# spotlight.net
KiCad netlist of a schematic drawn in EAGLE
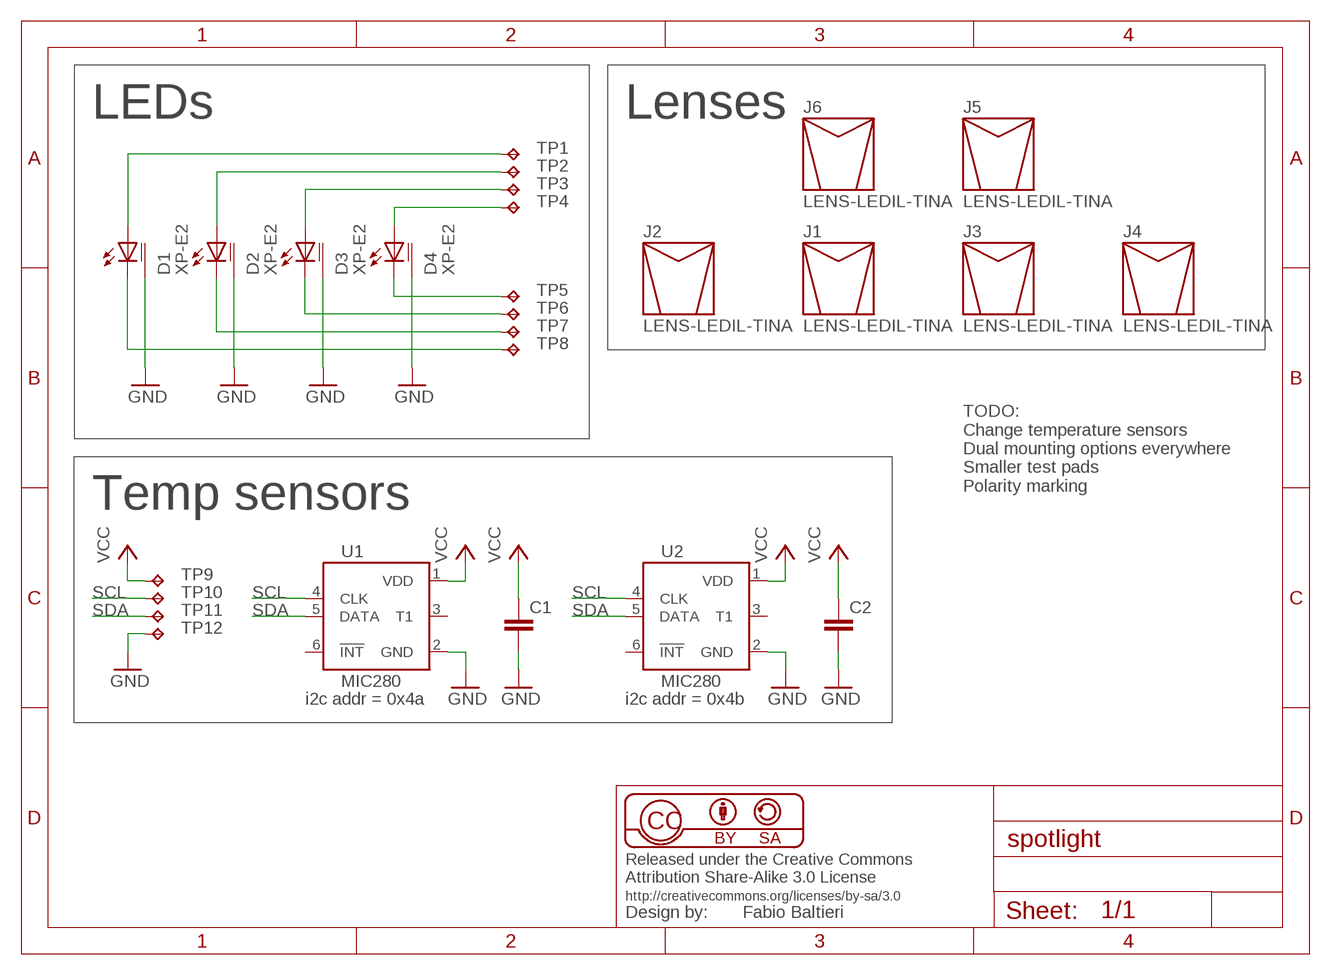
[diagram p0: schematic, sheet 1]

(export (version "E")
  (design (tool "Eeschema 10.0.6"))
  (components
    (comp (ref "C1")
      (value "C0603")
      (footprint "eagle-import:0603")
      (libsource (lib "eagle-import") (part "C0603"))
    )
    (comp (ref "C2")
      (value "C0603")
      (footprint "eagle-import:0603")
      (libsource (lib "eagle-import") (part "C0603"))
    )
    (comp (ref "D1")
      (value "XP-E2")
      (footprint "eagle-import:CREE_XPE")
      (libsource (lib "eagle-import") (part "LED_CREE-XP-E"))
    )
    (comp (ref "D2")
      (value "XP-E2")
      (footprint "eagle-import:CREE_XPE")
      (libsource (lib "eagle-import") (part "LED_CREE-XP-E"))
    )
    (comp (ref "D3")
      (value "XP-E2")
      (footprint "eagle-import:CREE_XPE")
      (libsource (lib "eagle-import") (part "LED_CREE-XP-E"))
    )
    (comp (ref "D4")
      (value "XP-E2")
      (footprint "eagle-import:CREE_XPE")
      (libsource (lib "eagle-import") (part "LED_CREE-XP-E"))
    )
    (comp (ref "J1")
      (value "LENS-LEDIL-TINA")
      (footprint "eagle-import:LEDIL-TINA")
      (libsource (lib "eagle-import") (part "LENS-LEDIL-TINA"))
    )
    (comp (ref "J2")
      (value "LENS-LEDIL-TINA")
      (footprint "eagle-import:LEDIL-TINA")
      (libsource (lib "eagle-import") (part "LENS-LEDIL-TINA"))
    )
    (comp (ref "J3")
      (value "LENS-LEDIL-TINA")
      (footprint "eagle-import:LEDIL-TINA")
      (libsource (lib "eagle-import") (part "LENS-LEDIL-TINA"))
    )
    (comp (ref "J4")
      (value "LENS-LEDIL-TINA")
      (footprint "eagle-import:LEDIL-TINA")
      (libsource (lib "eagle-import") (part "LENS-LEDIL-TINA"))
    )
    (comp (ref "J5")
      (value "LENS-LEDIL-TINA")
      (footprint "eagle-import:LEDIL-TINA")
      (libsource (lib "eagle-import") (part "LENS-LEDIL-TINA"))
    )
    (comp (ref "J6")
      (value "LENS-LEDIL-TINA")
      (footprint "eagle-import:LEDIL-TINA")
      (libsource (lib "eagle-import") (part "LENS-LEDIL-TINA"))
    )
    (comp (ref "TP1")
      (value "TPTP18R")
      (footprint "eagle-import:TP18R")
      (libsource (lib "eagle-import") (part "TPTP18R"))
    )
    (comp (ref "TP2")
      (value "TPTP18R")
      (footprint "eagle-import:TP18R")
      (libsource (lib "eagle-import") (part "TPTP18R"))
    )
    (comp (ref "TP3")
      (value "TPTP18R")
      (footprint "eagle-import:TP18R")
      (libsource (lib "eagle-import") (part "TPTP18R"))
    )
    (comp (ref "TP4")
      (value "TPTP18R")
      (footprint "eagle-import:TP18R")
      (libsource (lib "eagle-import") (part "TPTP18R"))
    )
    (comp (ref "TP5")
      (value "TPTP18R")
      (footprint "eagle-import:TP18R")
      (libsource (lib "eagle-import") (part "TPTP18R"))
    )
    (comp (ref "TP6")
      (value "TPTP18R")
      (footprint "eagle-import:TP18R")
      (libsource (lib "eagle-import") (part "TPTP18R"))
    )
    (comp (ref "TP7")
      (value "TPTP18R")
      (footprint "eagle-import:TP18R")
      (libsource (lib "eagle-import") (part "TPTP18R"))
    )
    (comp (ref "TP8")
      (value "TPTP18R")
      (footprint "eagle-import:TP18R")
      (libsource (lib "eagle-import") (part "TPTP18R"))
    )
    (comp (ref "TP9")
      (value "TPTP14R")
      (footprint "eagle-import:TP14R")
      (libsource (lib "eagle-import") (part "TPTP14R"))
    )
    (comp (ref "TP10")
      (value "TPTP14R")
      (footprint "eagle-import:TP14R")
      (libsource (lib "eagle-import") (part "TPTP14R"))
    )
    (comp (ref "TP11")
      (value "TPTP14R")
      (footprint "eagle-import:TP14R")
      (libsource (lib "eagle-import") (part "TPTP14R"))
    )
    (comp (ref "TP12")
      (value "TPTP14R")
      (footprint "eagle-import:TP14R")
      (libsource (lib "eagle-import") (part "TPTP14R"))
    )
    (comp (ref "U1")
      (value "MIC280")
      (footprint "eagle-import:SOT23-6L")
      (libsource (lib "eagle-import") (part "MIC280"))
    )
    (comp (ref "U2")
      (value "MIC280")
      (footprint "eagle-import:SOT23-6L")
      (libsource (lib "eagle-import") (part "MIC280"))
    )
  )
  (nets
    (net (code "1") (name "/SCL") (class "Default")
      (node (ref "TP10") (pin "TP") (pinfunction "TP_TP") (pintype "input"))
      (node (ref "U1") (pin "4") (pinfunction "CLK_4") (pintype "bidirectional"))
      (node (ref "U2") (pin "4") (pinfunction "CLK_4") (pintype "bidirectional"))
    )
    (net (code "2") (name "/SDA") (class "Default")
      (node (ref "TP11") (pin "TP") (pinfunction "TP_TP") (pintype "input"))
      (node (ref "U1") (pin "5") (pinfunction "DATA_5") (pintype "bidirectional"))
      (node (ref "U2") (pin "5") (pinfunction "DATA_5") (pintype "bidirectional"))
    )
    (net (code "3") (name "GND") (class "Default")
      (node (ref "C1") (pin "2") (pinfunction "2_2") (pintype "passive"))
      (node (ref "C2") (pin "2") (pinfunction "2_2") (pintype "passive"))
      (node (ref "D1") (pin "TH") (pinfunction "TH_TH") (pintype "passive"))
      (node (ref "D2") (pin "TH") (pinfunction "TH_TH") (pintype "passive"))
      (node (ref "D3") (pin "TH") (pinfunction "TH_TH") (pintype "passive"))
      (node (ref "D4") (pin "TH") (pinfunction "TH_TH") (pintype "passive"))
      (node (ref "TP12") (pin "TP") (pinfunction "TP_TP") (pintype "input"))
      (node (ref "U1") (pin "2") (pinfunction "GND_2") (pintype "bidirectional"))
      (node (ref "U2") (pin "2") (pinfunction "GND_2") (pintype "bidirectional"))
    )
    (net (code "4") (name "Net-(D1-C)") (class "Default")
      (node (ref "D1") (pin "K") (pinfunction "C_K") (pintype "passive"))
      (node (ref "TP8") (pin "TP") (pinfunction "TP_TP") (pintype "input"))
    )
    (net (code "5") (name "Net-(D1-PadA)") (class "Default")
      (node (ref "D1") (pin "A") (pinfunction "A_A") (pintype "passive"))
      (node (ref "TP1") (pin "TP") (pinfunction "TP_TP") (pintype "input"))
    )
    (net (code "6") (name "Net-(D2-C)") (class "Default")
      (node (ref "D2") (pin "K") (pinfunction "C_K") (pintype "passive"))
      (node (ref "TP7") (pin "TP") (pinfunction "TP_TP") (pintype "input"))
    )
    (net (code "7") (name "Net-(D2-PadA)") (class "Default")
      (node (ref "D2") (pin "A") (pinfunction "A_A") (pintype "passive"))
      (node (ref "TP2") (pin "TP") (pinfunction "TP_TP") (pintype "input"))
    )
    (net (code "8") (name "Net-(D3-C)") (class "Default")
      (node (ref "D3") (pin "K") (pinfunction "C_K") (pintype "passive"))
      (node (ref "TP6") (pin "TP") (pinfunction "TP_TP") (pintype "input"))
    )
    (net (code "9") (name "Net-(D3-PadA)") (class "Default")
      (node (ref "D3") (pin "A") (pinfunction "A_A") (pintype "passive"))
      (node (ref "TP3") (pin "TP") (pinfunction "TP_TP") (pintype "input"))
    )
    (net (code "10") (name "Net-(D4-C)") (class "Default")
      (node (ref "D4") (pin "K") (pinfunction "C_K") (pintype "passive"))
      (node (ref "TP5") (pin "TP") (pinfunction "TP_TP") (pintype "input"))
    )
    (net (code "11") (name "Net-(D4-PadA)") (class "Default")
      (node (ref "D4") (pin "A") (pinfunction "A_A") (pintype "passive"))
      (node (ref "TP4") (pin "TP") (pinfunction "TP_TP") (pintype "input"))
    )
    (net (code "12") (name "VCC") (class "Default")
      (node (ref "C1") (pin "1") (pinfunction "1_1") (pintype "passive"))
      (node (ref "C2") (pin "1") (pinfunction "1_1") (pintype "passive"))
      (node (ref "TP9") (pin "TP") (pinfunction "TP_TP") (pintype "input"))
      (node (ref "U1") (pin "1") (pinfunction "VDD_1") (pintype "bidirectional"))
      (node (ref "U2") (pin "1") (pinfunction "VDD_1") (pintype "bidirectional"))
    )
    (net (code "13") (name "unconnected-(U1-T1-Pad3)") (class "Default")
      (node (ref "U1") (pin "3") (pinfunction "T1_3") (pintype "bidirectional"))
    )
    (net (code "14") (name "unconnected-(U1-~{INT}-Pad6)") (class "Default")
      (node (ref "U1") (pin "6") (pinfunction "~{INT}_6") (pintype "bidirectional"))
    )
    (net (code "15") (name "unconnected-(U2-T1-Pad3)") (class "Default")
      (node (ref "U2") (pin "3") (pinfunction "T1_3") (pintype "bidirectional"))
    )
    (net (code "16") (name "unconnected-(U2-~{INT}-Pad6)") (class "Default")
      (node (ref "U2") (pin "6") (pinfunction "~{INT}_6") (pintype "bidirectional"))
    )
  )
)
